# x-bus-expander.net
KiCad netlist of a schematic drawn in EAGLE
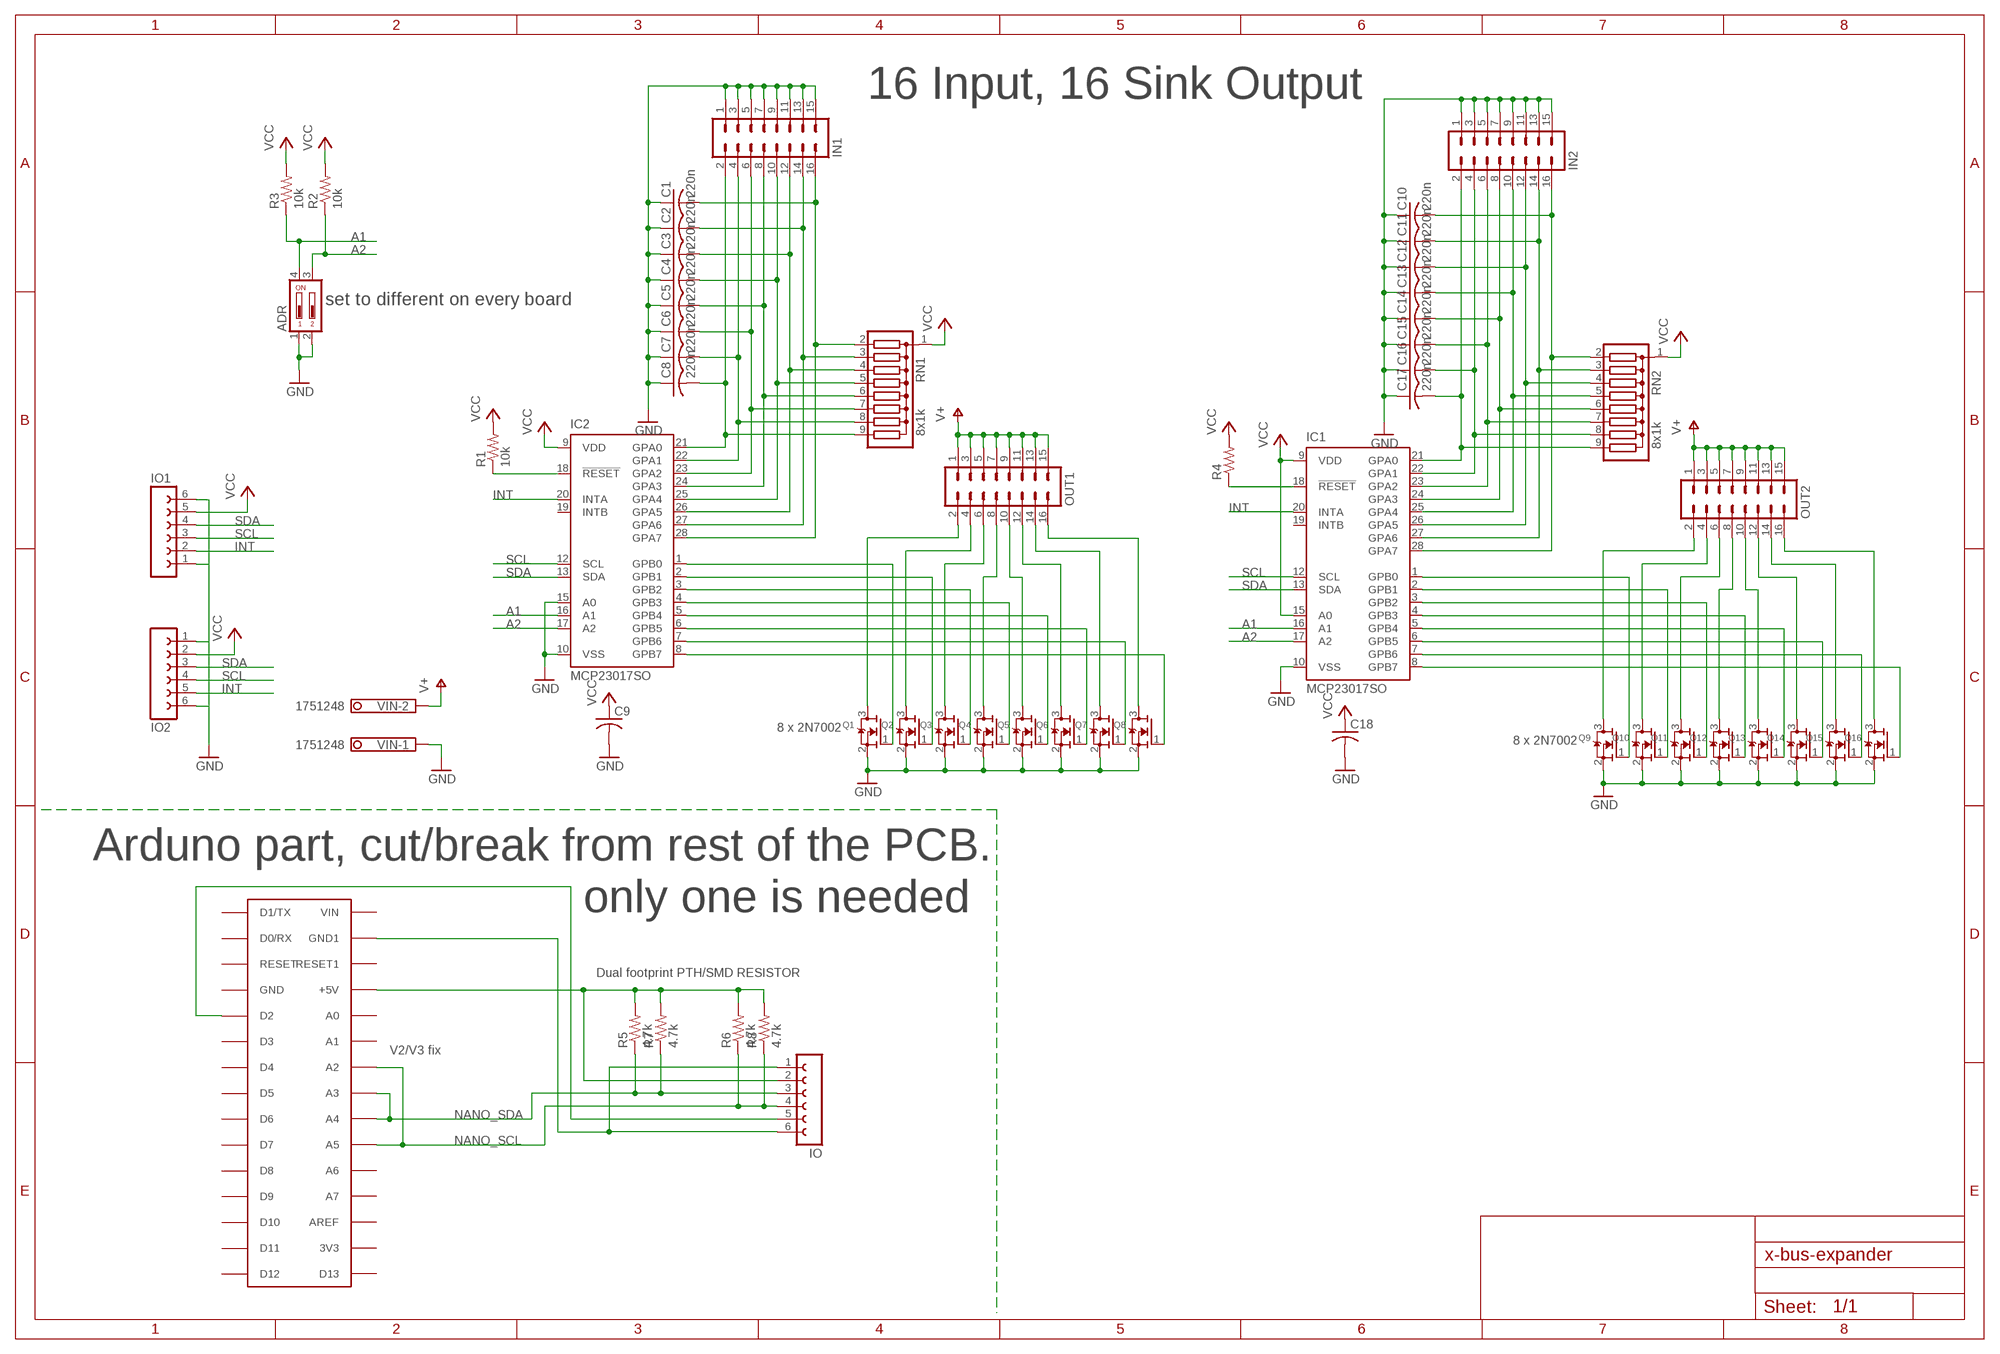
[diagram p0: schematic, sheet 1]

(export (version "E")
  (design (tool "Eeschema 10.0.6"))
  (components
    (comp (ref "ADR")
      (value "DIP02YL")
      (footprint "eagle-import:DIP02YL")
      (libsource (lib "eagle-import") (part "DIP02YL"))
    )
    (comp (ref "C1")
      (value "220n")
      (footprint "eagle-import:C0805")
      (libsource (lib "eagle-import") (part "C-USC0805"))
    )
    (comp (ref "C2")
      (value "220n")
      (footprint "eagle-import:C0805")
      (libsource (lib "eagle-import") (part "C-USC0805"))
    )
    (comp (ref "C3")
      (value "220n")
      (footprint "eagle-import:C0805")
      (libsource (lib "eagle-import") (part "C-USC0805"))
    )
    (comp (ref "C4")
      (value "220n")
      (footprint "eagle-import:C0805")
      (libsource (lib "eagle-import") (part "C-USC0805"))
    )
    (comp (ref "C5")
      (value "220n")
      (footprint "eagle-import:C0805")
      (libsource (lib "eagle-import") (part "C-USC0805"))
    )
    (comp (ref "C6")
      (value "220n")
      (footprint "eagle-import:C0805")
      (libsource (lib "eagle-import") (part "C-USC0805"))
    )
    (comp (ref "C7")
      (value "220n")
      (footprint "eagle-import:C0805")
      (libsource (lib "eagle-import") (part "C-USC0805"))
    )
    (comp (ref "C8")
      (value "220n")
      (footprint "eagle-import:C0805")
      (libsource (lib "eagle-import") (part "C-USC0805"))
    )
    (comp (ref "C9")
      (value "C-USC0805")
      (footprint "eagle-import:C0805")
      (libsource (lib "eagle-import") (part "C-USC0805"))
    )
    (comp (ref "C10")
      (value "220n")
      (footprint "eagle-import:C0805")
      (libsource (lib "eagle-import") (part "C-USC0805"))
    )
    (comp (ref "C11")
      (value "220n")
      (footprint "eagle-import:C0805")
      (libsource (lib "eagle-import") (part "C-USC0805"))
    )
    (comp (ref "C12")
      (value "220n")
      (footprint "eagle-import:C0805")
      (libsource (lib "eagle-import") (part "C-USC0805"))
    )
    (comp (ref "C13")
      (value "220n")
      (footprint "eagle-import:C0805")
      (libsource (lib "eagle-import") (part "C-USC0805"))
    )
    (comp (ref "C14")
      (value "220n")
      (footprint "eagle-import:C0805")
      (libsource (lib "eagle-import") (part "C-USC0805"))
    )
    (comp (ref "C15")
      (value "220n")
      (footprint "eagle-import:C0805")
      (libsource (lib "eagle-import") (part "C-USC0805"))
    )
    (comp (ref "C16")
      (value "220n")
      (footprint "eagle-import:C0805")
      (libsource (lib "eagle-import") (part "C-USC0805"))
    )
    (comp (ref "C17")
      (value "220n")
      (footprint "eagle-import:C0805")
      (libsource (lib "eagle-import") (part "C-USC0805"))
    )
    (comp (ref "C18")
      (value "C-USC0805")
      (footprint "eagle-import:C0805")
      (libsource (lib "eagle-import") (part "C-USC0805"))
    )
    (comp (ref "IC1")
      (value "MCP23017SO")
      (footprint "eagle-import:SO28W")
      (libsource (lib "eagle-import") (part "MCP23017SO"))
    )
    (comp (ref "IC2")
      (value "MCP23017SO")
      (footprint "eagle-import:SO28W")
      (libsource (lib "eagle-import") (part "MCP23017SO"))
    )
    (comp (ref "IN1")
      (value "ML16")
      (footprint "eagle-import:ML16")
      (libsource (lib "eagle-import") (part "ML16"))
    )
    (comp (ref "IN2")
      (value "ML16")
      (footprint "eagle-import:ML16")
      (libsource (lib "eagle-import") (part "ML16"))
    )
    (comp (ref "IO")
      (value "FE06W")
      (footprint "eagle-import:FE06W")
      (libsource (lib "eagle-import") (part "FE06W"))
    )
    (comp (ref "IO1")
      (value "FE06W")
      (footprint "eagle-import:FE06W")
      (libsource (lib "eagle-import") (part "FE06W"))
    )
    (comp (ref "IO2")
      (value "FE06W")
      (footprint "eagle-import:FE06W")
      (libsource (lib "eagle-import") (part "FE06W"))
    )
    (comp (ref "OUT1")
      (value "ML16")
      (footprint "eagle-import:ML16")
      (libsource (lib "eagle-import") (part "ML16"))
    )
    (comp (ref "OUT2")
      (value "ML16")
      (footprint "eagle-import:ML16")
      (libsource (lib "eagle-import") (part "ML16"))
    )
    (comp (ref "Q1")
      (value "MOSFET-NREFLOW")
      (footprint "eagle-import:SOT23")
      (libsource (lib "eagle-import") (part "MOSFET-NREFLOW"))
    )
    (comp (ref "Q2")
      (value "MOSFET-NREFLOW")
      (footprint "eagle-import:SOT23")
      (libsource (lib "eagle-import") (part "MOSFET-NREFLOW"))
    )
    (comp (ref "Q3")
      (value "MOSFET-NREFLOW")
      (footprint "eagle-import:SOT23")
      (libsource (lib "eagle-import") (part "MOSFET-NREFLOW"))
    )
    (comp (ref "Q4")
      (value "MOSFET-NREFLOW")
      (footprint "eagle-import:SOT23")
      (libsource (lib "eagle-import") (part "MOSFET-NREFLOW"))
    )
    (comp (ref "Q5")
      (value "MOSFET-NREFLOW")
      (footprint "eagle-import:SOT23")
      (libsource (lib "eagle-import") (part "MOSFET-NREFLOW"))
    )
    (comp (ref "Q6")
      (value "MOSFET-NREFLOW")
      (footprint "eagle-import:SOT23")
      (libsource (lib "eagle-import") (part "MOSFET-NREFLOW"))
    )
    (comp (ref "Q7")
      (value "MOSFET-NREFLOW")
      (footprint "eagle-import:SOT23")
      (libsource (lib "eagle-import") (part "MOSFET-NREFLOW"))
    )
    (comp (ref "Q8")
      (value "MOSFET-NREFLOW")
      (footprint "eagle-import:SOT23")
      (libsource (lib "eagle-import") (part "MOSFET-NREFLOW"))
    )
    (comp (ref "Q9")
      (value "MOSFET-NREFLOW")
      (footprint "eagle-import:SOT23")
      (libsource (lib "eagle-import") (part "MOSFET-NREFLOW"))
    )
    (comp (ref "Q10")
      (value "MOSFET-NREFLOW")
      (footprint "eagle-import:SOT23")
      (libsource (lib "eagle-import") (part "MOSFET-NREFLOW"))
    )
    (comp (ref "Q11")
      (value "MOSFET-NREFLOW")
      (footprint "eagle-import:SOT23")
      (libsource (lib "eagle-import") (part "MOSFET-NREFLOW"))
    )
    (comp (ref "Q12")
      (value "MOSFET-NREFLOW")
      (footprint "eagle-import:SOT23")
      (libsource (lib "eagle-import") (part "MOSFET-NREFLOW"))
    )
    (comp (ref "Q13")
      (value "MOSFET-NREFLOW")
      (footprint "eagle-import:SOT23")
      (libsource (lib "eagle-import") (part "MOSFET-NREFLOW"))
    )
    (comp (ref "Q14")
      (value "MOSFET-NREFLOW")
      (footprint "eagle-import:SOT23")
      (libsource (lib "eagle-import") (part "MOSFET-NREFLOW"))
    )
    (comp (ref "Q15")
      (value "MOSFET-NREFLOW")
      (footprint "eagle-import:SOT23")
      (libsource (lib "eagle-import") (part "MOSFET-NREFLOW"))
    )
    (comp (ref "Q16")
      (value "MOSFET-NREFLOW")
      (footprint "eagle-import:SOT23")
      (libsource (lib "eagle-import") (part "MOSFET-NREFLOW"))
    )
    (comp (ref "R1")
      (value "10k")
      (footprint "eagle-import:R0603")
      (libsource (lib "eagle-import") (part "R-US_R0603"))
    )
    (comp (ref "R2")
      (value "10k")
      (footprint "eagle-import:R0603")
      (libsource (lib "eagle-import") (part "R-US_R0603"))
    )
    (comp (ref "R3")
      (value "10k")
      (footprint "eagle-import:R0603")
      (libsource (lib "eagle-import") (part "R-US_R0603"))
    )
    (comp (ref "R4")
      (value "R-US_R0603")
      (footprint "eagle-import:R0603")
      (libsource (lib "eagle-import") (part "R-US_R0603"))
    )
    (comp (ref "R5")
      (value "4.7k")
      (footprint "eagle-import:0309_10")
      (libsource (lib "eagle-import") (part "R-US_0309/10"))
    )
    (comp (ref "R6")
      (value "4.7k")
      (footprint "eagle-import:0309_10")
      (libsource (lib "eagle-import") (part "R-US_0309/10"))
    )
    (comp (ref "R7")
      (value "4.7k")
      (footprint "eagle-import:R0603")
      (libsource (lib "eagle-import") (part "R-US_R0603"))
    )
    (comp (ref "R8")
      (value "4.7k")
      (footprint "eagle-import:R0603")
      (libsource (lib "eagle-import") (part "R-US_R0603"))
    )
    (comp (ref "RN1")
      (value "8x1k")
      (footprint "eagle-import:SIL9")
      (libsource (lib "eagle-import") (part "G08R"))
    )
    (comp (ref "RN2")
      (value "8x1k")
      (footprint "eagle-import:SIL9")
      (libsource (lib "eagle-import") (part "G08R"))
    )
    (comp (ref "U$1")
      (value "ARDUINONANO")
      (footprint "eagle-import:PDIP-32")
      (libsource (lib "eagle-import") (part "ARDUINONANO"))
    )
    (comp (ref "VIN")
      (value "1751248")
      (footprint "eagle-import:1751248")
      (libsource (lib "eagle-import") (part "1751248"))
    )
  )
  (nets
    (net (code "1") (name "/A1") (class "Default")
      (node (ref "ADR") (pin "4") (pinfunction "4_4") (pintype "passive"))
      (node (ref "IC1") (pin "16") (pinfunction "A1_16") (pintype "input"))
      (node (ref "IC2") (pin "16") (pinfunction "A1_16") (pintype "input"))
      (node (ref "R3") (pin "1") (pinfunction "1_1") (pintype "passive"))
    )
    (net (code "2") (name "/A2") (class "Default")
      (node (ref "ADR") (pin "3") (pinfunction "3_3") (pintype "passive"))
      (node (ref "IC1") (pin "17") (pinfunction "A2_17") (pintype "input"))
      (node (ref "IC2") (pin "17") (pinfunction "A2_17") (pintype "input"))
      (node (ref "R2") (pin "1") (pinfunction "1_1") (pintype "passive"))
    )
    (net (code "3") (name "/INT") (class "Default")
      (node (ref "IC1") (pin "20") (pinfunction "INTA_20") (pintype "output"))
      (node (ref "IC2") (pin "20") (pinfunction "INTA_20") (pintype "output"))
      (node (ref "IO1") (pin "2") (pinfunction "2_2") (pintype "passive"))
      (node (ref "IO2") (pin "5") (pinfunction "5_5") (pintype "passive"))
    )
    (net (code "4") (name "/NANO_SCL") (class "Default")
      (node (ref "IO") (pin "4") (pinfunction "4_4") (pintype "passive"))
      (node (ref "R6") (pin "1") (pinfunction "1_1") (pintype "passive"))
      (node (ref "R8") (pin "1") (pinfunction "1_1") (pintype "passive"))
      (node (ref "U$1") (pin "A2") (pinfunction "A2_A2") (pintype "bidirectional"))
      (node (ref "U$1") (pin "A5") (pinfunction "A5_A5") (pintype "bidirectional"))
    )
    (net (code "5") (name "/NANO_SDA") (class "Default")
      (node (ref "IO") (pin "3") (pinfunction "3_3") (pintype "passive"))
      (node (ref "R5") (pin "1") (pinfunction "1_1") (pintype "passive"))
      (node (ref "R7") (pin "1") (pinfunction "1_1") (pintype "passive"))
      (node (ref "U$1") (pin "A3") (pinfunction "A3_A3") (pintype "bidirectional"))
      (node (ref "U$1") (pin "A4") (pinfunction "A4_A4") (pintype "bidirectional"))
    )
    (net (code "6") (name "/SCL") (class "Default")
      (node (ref "IC1") (pin "12") (pinfunction "SCL_12") (pintype "input"))
      (node (ref "IC2") (pin "12") (pinfunction "SCL_12") (pintype "input"))
      (node (ref "IO1") (pin "3") (pinfunction "3_3") (pintype "passive"))
      (node (ref "IO2") (pin "4") (pinfunction "4_4") (pintype "passive"))
    )
    (net (code "7") (name "/SDA") (class "Default")
      (node (ref "IC1") (pin "13") (pinfunction "SDA_13") (pintype "bidirectional"))
      (node (ref "IC2") (pin "13") (pinfunction "SDA_13") (pintype "bidirectional"))
      (node (ref "IO1") (pin "4") (pinfunction "4_4") (pintype "passive"))
      (node (ref "IO2") (pin "3") (pinfunction "3_3") (pintype "passive"))
    )
    (net (code "8") (name "GND") (class "Default")
      (node (ref "ADR") (pin "1") (pinfunction "1_1") (pintype "passive"))
      (node (ref "ADR") (pin "2") (pinfunction "2_2") (pintype "passive"))
      (node (ref "C1") (pin "1") (pinfunction "1_1") (pintype "passive"))
      (node (ref "C10") (pin "1") (pinfunction "1_1") (pintype "passive"))
      (node (ref "C11") (pin "1") (pinfunction "1_1") (pintype "passive"))
      (node (ref "C12") (pin "1") (pinfunction "1_1") (pintype "passive"))
      (node (ref "C13") (pin "1") (pinfunction "1_1") (pintype "passive"))
      (node (ref "C14") (pin "1") (pinfunction "1_1") (pintype "passive"))
      (node (ref "C15") (pin "1") (pinfunction "1_1") (pintype "passive"))
      (node (ref "C16") (pin "1") (pinfunction "1_1") (pintype "passive"))
      (node (ref "C17") (pin "1") (pinfunction "1_1") (pintype "passive"))
      (node (ref "C18") (pin "2") (pinfunction "2_2") (pintype "passive"))
      (node (ref "C2") (pin "1") (pinfunction "1_1") (pintype "passive"))
      (node (ref "C3") (pin "1") (pinfunction "1_1") (pintype "passive"))
      (node (ref "C4") (pin "1") (pinfunction "1_1") (pintype "passive"))
      (node (ref "C5") (pin "1") (pinfunction "1_1") (pintype "passive"))
      (node (ref "C6") (pin "1") (pinfunction "1_1") (pintype "passive"))
      (node (ref "C7") (pin "1") (pinfunction "1_1") (pintype "passive"))
      (node (ref "C8") (pin "1") (pinfunction "1_1") (pintype "passive"))
      (node (ref "C9") (pin "2") (pinfunction "2_2") (pintype "passive"))
      (node (ref "IC1") (pin "10") (pinfunction "VSS_10") (pintype "power_in"))
      (node (ref "IC2") (pin "10") (pinfunction "VSS_10") (pintype "power_in"))
      (node (ref "IC2") (pin "15") (pinfunction "A0_15") (pintype "input"))
      (node (ref "IN1") (pin "1") (pinfunction "1_1") (pintype "passive"))
      (node (ref "IN1") (pin "11") (pinfunction "11_11") (pintype "passive"))
      (node (ref "IN1") (pin "13") (pinfunction "13_13") (pintype "passive"))
      (node (ref "IN1") (pin "15") (pinfunction "15_15") (pintype "passive"))
      (node (ref "IN1") (pin "3") (pinfunction "3_3") (pintype "passive"))
      (node (ref "IN1") (pin "5") (pinfunction "5_5") (pintype "passive"))
      (node (ref "IN1") (pin "7") (pinfunction "7_7") (pintype "passive"))
      (node (ref "IN1") (pin "9") (pinfunction "9_9") (pintype "passive"))
      (node (ref "IN2") (pin "1") (pinfunction "1_1") (pintype "passive"))
      (node (ref "IN2") (pin "11") (pinfunction "11_11") (pintype "passive"))
      (node (ref "IN2") (pin "13") (pinfunction "13_13") (pintype "passive"))
      (node (ref "IN2") (pin "15") (pinfunction "15_15") (pintype "passive"))
      (node (ref "IN2") (pin "3") (pinfunction "3_3") (pintype "passive"))
      (node (ref "IN2") (pin "5") (pinfunction "5_5") (pintype "passive"))
      (node (ref "IN2") (pin "7") (pinfunction "7_7") (pintype "passive"))
      (node (ref "IN2") (pin "9") (pinfunction "9_9") (pintype "passive"))
      (node (ref "IO1") (pin "1") (pinfunction "1_1") (pintype "passive"))
      (node (ref "IO1") (pin "6") (pinfunction "6_6") (pintype "passive"))
      (node (ref "IO2") (pin "1") (pinfunction "1_1") (pintype "passive"))
      (node (ref "IO2") (pin "6") (pinfunction "6_6") (pintype "passive"))
      (node (ref "Q1") (pin "2") (pinfunction "S_2") (pintype "bidirectional"))
      (node (ref "Q10") (pin "2") (pinfunction "S_2") (pintype "bidirectional"))
      (node (ref "Q11") (pin "2") (pinfunction "S_2") (pintype "bidirectional"))
      (node (ref "Q12") (pin "2") (pinfunction "S_2") (pintype "bidirectional"))
      (node (ref "Q13") (pin "2") (pinfunction "S_2") (pintype "bidirectional"))
      (node (ref "Q14") (pin "2") (pinfunction "S_2") (pintype "bidirectional"))
      (node (ref "Q15") (pin "2") (pinfunction "S_2") (pintype "bidirectional"))
      (node (ref "Q16") (pin "2") (pinfunction "S_2") (pintype "bidirectional"))
      (node (ref "Q2") (pin "2") (pinfunction "S_2") (pintype "bidirectional"))
      (node (ref "Q3") (pin "2") (pinfunction "S_2") (pintype "bidirectional"))
      (node (ref "Q4") (pin "2") (pinfunction "S_2") (pintype "bidirectional"))
      (node (ref "Q5") (pin "2") (pinfunction "S_2") (pintype "bidirectional"))
      (node (ref "Q6") (pin "2") (pinfunction "S_2") (pintype "bidirectional"))
      (node (ref "Q7") (pin "2") (pinfunction "S_2") (pintype "bidirectional"))
      (node (ref "Q8") (pin "2") (pinfunction "S_2") (pintype "bidirectional"))
      (node (ref "Q9") (pin "2") (pinfunction "S_2") (pintype "bidirectional"))
      (node (ref "VIN") (pin "1") (pinfunction "K_1") (pintype "passive"))
    )
    (net (code "9") (name "Net-(IC1-GPA0)") (class "Default")
      (node (ref "C17") (pin "2") (pinfunction "2_2") (pintype "passive"))
      (node (ref "IC1") (pin "21") (pinfunction "GPA0_21") (pintype "bidirectional"))
      (node (ref "IN2") (pin "2") (pinfunction "2_2") (pintype "passive"))
      (node (ref "RN2") (pin "9") (pinfunction "9_9") (pintype "passive"))
    )
    (net (code "10") (name "Net-(IC1-GPA1)") (class "Default")
      (node (ref "C16") (pin "2") (pinfunction "2_2") (pintype "passive"))
      (node (ref "IC1") (pin "22") (pinfunction "GPA1_22") (pintype "bidirectional"))
      (node (ref "IN2") (pin "4") (pinfunction "4_4") (pintype "passive"))
      (node (ref "RN2") (pin "8") (pinfunction "8_8") (pintype "passive"))
    )
    (net (code "11") (name "Net-(IC1-GPA2)") (class "Default")
      (node (ref "C15") (pin "2") (pinfunction "2_2") (pintype "passive"))
      (node (ref "IC1") (pin "23") (pinfunction "GPA2_23") (pintype "bidirectional"))
      (node (ref "IN2") (pin "6") (pinfunction "6_6") (pintype "passive"))
      (node (ref "RN2") (pin "7") (pinfunction "7_7") (pintype "passive"))
    )
    (net (code "12") (name "Net-(IC1-GPA3)") (class "Default")
      (node (ref "C14") (pin "2") (pinfunction "2_2") (pintype "passive"))
      (node (ref "IC1") (pin "24") (pinfunction "GPA3_24") (pintype "bidirectional"))
      (node (ref "IN2") (pin "8") (pinfunction "8_8") (pintype "passive"))
      (node (ref "RN2") (pin "6") (pinfunction "6_6") (pintype "passive"))
    )
    (net (code "13") (name "Net-(IC1-GPA4)") (class "Default")
      (node (ref "C13") (pin "2") (pinfunction "2_2") (pintype "passive"))
      (node (ref "IC1") (pin "25") (pinfunction "GPA4_25") (pintype "bidirectional"))
      (node (ref "IN2") (pin "10") (pinfunction "10_10") (pintype "passive"))
      (node (ref "RN2") (pin "5") (pinfunction "5_5") (pintype "passive"))
    )
    (net (code "14") (name "Net-(IC1-GPA5)") (class "Default")
      (node (ref "C12") (pin "2") (pinfunction "2_2") (pintype "passive"))
      (node (ref "IC1") (pin "26") (pinfunction "GPA5_26") (pintype "bidirectional"))
      (node (ref "IN2") (pin "12") (pinfunction "12_12") (pintype "passive"))
      (node (ref "RN2") (pin "4") (pinfunction "4_4") (pintype "passive"))
    )
    (net (code "15") (name "Net-(IC1-GPA6)") (class "Default")
      (node (ref "C11") (pin "2") (pinfunction "2_2") (pintype "passive"))
      (node (ref "IC1") (pin "27") (pinfunction "GPA6_27") (pintype "bidirectional"))
      (node (ref "IN2") (pin "14") (pinfunction "14_14") (pintype "passive"))
      (node (ref "RN2") (pin "3") (pinfunction "3_3") (pintype "passive"))
    )
    (net (code "16") (name "Net-(IC1-GPA7)") (class "Default")
      (node (ref "C10") (pin "2") (pinfunction "2_2") (pintype "passive"))
      (node (ref "IC1") (pin "28") (pinfunction "GPA7_28") (pintype "bidirectional"))
      (node (ref "IN2") (pin "16") (pinfunction "16_16") (pintype "passive"))
      (node (ref "RN2") (pin "2") (pinfunction "2_2") (pintype "passive"))
    )
    (net (code "17") (name "Net-(IC1-GPB0)") (class "Default")
      (node (ref "IC1") (pin "1") (pinfunction "GPB0_1") (pintype "bidirectional"))
      (node (ref "Q9") (pin "1") (pinfunction "G_1") (pintype "bidirectional"))
    )
    (net (code "18") (name "Net-(IC1-GPB1)") (class "Default")
      (node (ref "IC1") (pin "2") (pinfunction "GPB1_2") (pintype "bidirectional"))
      (node (ref "Q10") (pin "1") (pinfunction "G_1") (pintype "bidirectional"))
    )
    (net (code "19") (name "Net-(IC1-GPB2)") (class "Default")
      (node (ref "IC1") (pin "3") (pinfunction "GPB2_3") (pintype "bidirectional"))
      (node (ref "Q11") (pin "1") (pinfunction "G_1") (pintype "bidirectional"))
    )
    (net (code "20") (name "Net-(IC1-GPB3)") (class "Default")
      (node (ref "IC1") (pin "4") (pinfunction "GPB3_4") (pintype "bidirectional"))
      (node (ref "Q12") (pin "1") (pinfunction "G_1") (pintype "bidirectional"))
    )
    (net (code "21") (name "Net-(IC1-GPB4)") (class "Default")
      (node (ref "IC1") (pin "5") (pinfunction "GPB4_5") (pintype "bidirectional"))
      (node (ref "Q13") (pin "1") (pinfunction "G_1") (pintype "bidirectional"))
    )
    (net (code "22") (name "Net-(IC1-GPB5)") (class "Default")
      (node (ref "IC1") (pin "6") (pinfunction "GPB5_6") (pintype "bidirectional"))
      (node (ref "Q14") (pin "1") (pinfunction "G_1") (pintype "bidirectional"))
    )
    (net (code "23") (name "Net-(IC1-GPB6)") (class "Default")
      (node (ref "IC1") (pin "7") (pinfunction "GPB6_7") (pintype "bidirectional"))
      (node (ref "Q15") (pin "1") (pinfunction "G_1") (pintype "bidirectional"))
    )
    (net (code "24") (name "Net-(IC1-GPB7)") (class "Default")
      (node (ref "IC1") (pin "8") (pinfunction "GPB7_8") (pintype "bidirectional"))
      (node (ref "Q16") (pin "1") (pinfunction "G_1") (pintype "bidirectional"))
    )
    (net (code "25") (name "Net-(IC1-~{RESET})") (class "Default")
      (node (ref "IC1") (pin "18") (pinfunction "~{RESET}_18") (pintype "input"))
      (node (ref "R4") (pin "1") (pinfunction "1_1") (pintype "passive"))
    )
    (net (code "26") (name "Net-(IC2-GPA0)") (class "Default")
      (node (ref "C8") (pin "2") (pinfunction "2_2") (pintype "passive"))
      (node (ref "IC2") (pin "21") (pinfunction "GPA0_21") (pintype "bidirectional"))
      (node (ref "IN1") (pin "2") (pinfunction "2_2") (pintype "passive"))
      (node (ref "RN1") (pin "9") (pinfunction "9_9") (pintype "passive"))
    )
    (net (code "27") (name "Net-(IC2-GPA1)") (class "Default")
      (node (ref "C7") (pin "2") (pinfunction "2_2") (pintype "passive"))
      (node (ref "IC2") (pin "22") (pinfunction "GPA1_22") (pintype "bidirectional"))
      (node (ref "IN1") (pin "4") (pinfunction "4_4") (pintype "passive"))
      (node (ref "RN1") (pin "8") (pinfunction "8_8") (pintype "passive"))
    )
    (net (code "28") (name "Net-(IC2-GPA2)") (class "Default")
      (node (ref "C6") (pin "2") (pinfunction "2_2") (pintype "passive"))
      (node (ref "IC2") (pin "23") (pinfunction "GPA2_23") (pintype "bidirectional"))
      (node (ref "IN1") (pin "6") (pinfunction "6_6") (pintype "passive"))
      (node (ref "RN1") (pin "7") (pinfunction "7_7") (pintype "passive"))
    )
    (net (code "29") (name "Net-(IC2-GPA3)") (class "Default")
      (node (ref "C5") (pin "2") (pinfunction "2_2") (pintype "passive"))
      (node (ref "IC2") (pin "24") (pinfunction "GPA3_24") (pintype "bidirectional"))
      (node (ref "IN1") (pin "8") (pinfunction "8_8") (pintype "passive"))
      (node (ref "RN1") (pin "6") (pinfunction "6_6") (pintype "passive"))
    )
    (net (code "30") (name "Net-(IC2-GPA4)") (class "Default")
      (node (ref "C4") (pin "2") (pinfunction "2_2") (pintype "passive"))
      (node (ref "IC2") (pin "25") (pinfunction "GPA4_25") (pintype "bidirectional"))
      (node (ref "IN1") (pin "10") (pinfunction "10_10") (pintype "passive"))
      (node (ref "RN1") (pin "5") (pinfunction "5_5") (pintype "passive"))
    )
    (net (code "31") (name "Net-(IC2-GPA5)") (class "Default")
      (node (ref "C3") (pin "2") (pinfunction "2_2") (pintype "passive"))
      (node (ref "IC2") (pin "26") (pinfunction "GPA5_26") (pintype "bidirectional"))
      (node (ref "IN1") (pin "12") (pinfunction "12_12") (pintype "passive"))
      (node (ref "RN1") (pin "4") (pinfunction "4_4") (pintype "passive"))
    )
    (net (code "32") (name "Net-(IC2-GPA6)") (class "Default")
      (node (ref "C2") (pin "2") (pinfunction "2_2") (pintype "passive"))
      (node (ref "IC2") (pin "27") (pinfunction "GPA6_27") (pintype "bidirectional"))
      (node (ref "IN1") (pin "14") (pinfunction "14_14") (pintype "passive"))
      (node (ref "RN1") (pin "3") (pinfunction "3_3") (pintype "passive"))
    )
    (net (code "33") (name "Net-(IC2-GPA7)") (class "Default")
      (node (ref "C1") (pin "2") (pinfunction "2_2") (pintype "passive"))
      (node (ref "IC2") (pin "28") (pinfunction "GPA7_28") (pintype "bidirectional"))
      (node (ref "IN1") (pin "16") (pinfunction "16_16") (pintype "passive"))
      (node (ref "RN1") (pin "2") (pinfunction "2_2") (pintype "passive"))
    )
    (net (code "34") (name "Net-(IC2-GPB0)") (class "Default")
      (node (ref "IC2") (pin "1") (pinfunction "GPB0_1") (pintype "bidirectional"))
      (node (ref "Q1") (pin "1") (pinfunction "G_1") (pintype "bidirectional"))
    )
    (net (code "35") (name "Net-(IC2-GPB1)") (class "Default")
      (node (ref "IC2") (pin "2") (pinfunction "GPB1_2") (pintype "bidirectional"))
      (node (ref "Q2") (pin "1") (pinfunction "G_1") (pintype "bidirectional"))
    )
    (net (code "36") (name "Net-(IC2-GPB2)") (class "Default")
      (node (ref "IC2") (pin "3") (pinfunction "GPB2_3") (pintype "bidirectional"))
      (node (ref "Q3") (pin "1") (pinfunction "G_1") (pintype "bidirectional"))
    )
    (net (code "37") (name "Net-(IC2-GPB3)") (class "Default")
      (node (ref "IC2") (pin "4") (pinfunction "GPB3_4") (pintype "bidirectional"))
      (node (ref "Q4") (pin "1") (pinfunction "G_1") (pintype "bidirectional"))
    )
    (net (code "38") (name "Net-(IC2-GPB4)") (class "Default")
      (node (ref "IC2") (pin "5") (pinfunction "GPB4_5") (pintype "bidirectional"))
      (node (ref "Q5") (pin "1") (pinfunction "G_1") (pintype "bidirectional"))
    )
    (net (code "39") (name "Net-(IC2-GPB5)") (class "Default")
      (node (ref "IC2") (pin "6") (pinfunction "GPB5_6") (pintype "bidirectional"))
      (node (ref "Q6") (pin "1") (pinfunction "G_1") (pintype "bidirectional"))
    )
    (net (code "40") (name "Net-(IC2-GPB6)") (class "Default")
      (node (ref "IC2") (pin "7") (pinfunction "GPB6_7") (pintype "bidirectional"))
      (node (ref "Q7") (pin "1") (pinfunction "G_1") (pintype "bidirectional"))
    )
    (net (code "41") (name "Net-(IC2-GPB7)") (class "Default")
      (node (ref "IC2") (pin "8") (pinfunction "GPB7_8") (pintype "bidirectional"))
      (node (ref "Q8") (pin "1") (pinfunction "G_1") (pintype "bidirectional"))
    )
    (net (code "42") (name "Net-(IC2-~{RESET})") (class "Default")
      (node (ref "IC2") (pin "18") (pinfunction "~{RESET}_18") (pintype "input"))
      (node (ref "R1") (pin "1") (pinfunction "1_1") (pintype "passive"))
    )
    (net (code "43") (name "Net-(IO-Pad1)") (class "Default")
      (node (ref "IO") (pin "1") (pinfunction "1_1") (pintype "passive"))
      (node (ref "IO") (pin "6") (pinfunction "6_6") (pintype "passive"))
      (node (ref "U$1") (pin "GND1") (pinfunction "GND1_GND1") (pintype "bidirectional"))
    )
    (net (code "44") (name "Net-(IO-Pad2)") (class "Default")
      (node (ref "IO") (pin "2") (pinfunction "2_2") (pintype "passive"))
      (node (ref "R5") (pin "2") (pinfunction "2_2") (pintype "passive"))
      (node (ref "R6") (pin "2") (pinfunction "2_2") (pintype "passive"))
      (node (ref "R7") (pin "2") (pinfunction "2_2") (pintype "passive"))
      (node (ref "R8") (pin "2") (pinfunction "2_2") (pintype "passive"))
      (node (ref "U$1") (pin "+5V") (pinfunction "+5V_+5V") (pintype "bidirectional"))
    )
    (net (code "45") (name "Net-(IO-Pad5)") (class "Default")
      (node (ref "IO") (pin "5") (pinfunction "5_5") (pintype "passive"))
      (node (ref "U$1") (pin "D2") (pinfunction "D2_D2") (pintype "bidirectional"))
    )
    (net (code "46") (name "Net-(Q1-D)") (class "Default")
      (node (ref "OUT1") (pin "2") (pinfunction "2_2") (pintype "passive"))
      (node (ref "Q1") (pin "3") (pinfunction "D_3") (pintype "bidirectional"))
    )
    (net (code "47") (name "Net-(Q2-D)") (class "Default")
      (node (ref "OUT1") (pin "4") (pinfunction "4_4") (pintype "passive"))
      (node (ref "Q2") (pin "3") (pinfunction "D_3") (pintype "bidirectional"))
    )
    (net (code "48") (name "Net-(Q3-D)") (class "Default")
      (node (ref "OUT1") (pin "6") (pinfunction "6_6") (pintype "passive"))
      (node (ref "Q3") (pin "3") (pinfunction "D_3") (pintype "bidirectional"))
    )
    (net (code "49") (name "Net-(Q4-D)") (class "Default")
      (node (ref "OUT1") (pin "8") (pinfunction "8_8") (pintype "passive"))
      (node (ref "Q4") (pin "3") (pinfunction "D_3") (pintype "bidirectional"))
    )
    (net (code "50") (name "Net-(Q5-D)") (class "Default")
      (node (ref "OUT1") (pin "10") (pinfunction "10_10") (pintype "passive"))
      (node (ref "Q5") (pin "3") (pinfunction "D_3") (pintype "bidirectional"))
    )
    (net (code "51") (name "Net-(Q6-D)") (class "Default")
      (node (ref "OUT1") (pin "12") (pinfunction "12_12") (pintype "passive"))
      (node (ref "Q6") (pin "3") (pinfunction "D_3") (pintype "bidirectional"))
    )
    (net (code "52") (name "Net-(Q7-D)") (class "Default")
      (node (ref "OUT1") (pin "14") (pinfunction "14_14") (pintype "passive"))
      (node (ref "Q7") (pin "3") (pinfunction "D_3") (pintype "bidirectional"))
    )
    (net (code "53") (name "Net-(Q8-D)") (class "Default")
      (node (ref "OUT1") (pin "16") (pinfunction "16_16") (pintype "passive"))
      (node (ref "Q8") (pin "3") (pinfunction "D_3") (pintype "bidirectional"))
    )
    (net (code "54") (name "Net-(Q9-D)") (class "Default")
      (node (ref "OUT2") (pin "2") (pinfunction "2_2") (pintype "passive"))
      (node (ref "Q9") (pin "3") (pinfunction "D_3") (pintype "bidirectional"))
    )
    (net (code "55") (name "Net-(Q10-D)") (class "Default")
      (node (ref "OUT2") (pin "4") (pinfunction "4_4") (pintype "passive"))
      (node (ref "Q10") (pin "3") (pinfunction "D_3") (pintype "bidirectional"))
    )
    (net (code "56") (name "Net-(Q11-D)") (class "Default")
      (node (ref "OUT2") (pin "6") (pinfunction "6_6") (pintype "passive"))
      (node (ref "Q11") (pin "3") (pinfunction "D_3") (pintype "bidirectional"))
    )
    (net (code "57") (name "Net-(Q12-D)") (class "Default")
      (node (ref "OUT2") (pin "8") (pinfunction "8_8") (pintype "passive"))
      (node (ref "Q12") (pin "3") (pinfunction "D_3") (pintype "bidirectional"))
    )
    (net (code "58") (name "Net-(Q13-D)") (class "Default")
      (node (ref "OUT2") (pin "10") (pinfunction "10_10") (pintype "passive"))
      (node (ref "Q13") (pin "3") (pinfunction "D_3") (pintype "bidirectional"))
    )
    (net (code "59") (name "Net-(Q14-D)") (class "Default")
      (node (ref "OUT2") (pin "12") (pinfunction "12_12") (pintype "passive"))
      (node (ref "Q14") (pin "3") (pinfunction "D_3") (pintype "bidirectional"))
    )
    (net (code "60") (name "Net-(Q15-D)") (class "Default")
      (node (ref "OUT2") (pin "14") (pinfunction "14_14") (pintype "passive"))
      (node (ref "Q15") (pin "3") (pinfunction "D_3") (pintype "bidirectional"))
    )
    (net (code "61") (name "Net-(Q16-D)") (class "Default")
      (node (ref "OUT2") (pin "16") (pinfunction "16_16") (pintype "passive"))
      (node (ref "Q16") (pin "3") (pinfunction "D_3") (pintype "bidirectional"))
    )
    (net (code "62") (name "V+") (class "Default")
      (node (ref "OUT1") (pin "1") (pinfunction "1_1") (pintype "passive"))
      (node (ref "OUT1") (pin "11") (pinfunction "11_11") (pintype "passive"))
      (node (ref "OUT1") (pin "13") (pinfunction "13_13") (pintype "passive"))
      (node (ref "OUT1") (pin "15") (pinfunction "15_15") (pintype "passive"))
      (node (ref "OUT1") (pin "3") (pinfunction "3_3") (pintype "passive"))
      (node (ref "OUT1") (pin "5") (pinfunction "5_5") (pintype "passive"))
      (node (ref "OUT1") (pin "7") (pinfunction "7_7") (pintype "passive"))
      (node (ref "OUT1") (pin "9") (pinfunction "9_9") (pintype "passive"))
      (node (ref "OUT2") (pin "1") (pinfunction "1_1") (pintype "passive"))
      (node (ref "OUT2") (pin "11") (pinfunction "11_11") (pintype "passive"))
      (node (ref "OUT2") (pin "13") (pinfunction "13_13") (pintype "passive"))
      (node (ref "OUT2") (pin "15") (pinfunction "15_15") (pintype "passive"))
      (node (ref "OUT2") (pin "3") (pinfunction "3_3") (pintype "passive"))
      (node (ref "OUT2") (pin "5") (pinfunction "5_5") (pintype "passive"))
      (node (ref "OUT2") (pin "7") (pinfunction "7_7") (pintype "passive"))
      (node (ref "OUT2") (pin "9") (pinfunction "9_9") (pintype "passive"))
      (node (ref "VIN") (pin "2") (pinfunction "K_2") (pintype "passive"))
    )
    (net (code "63") (name "VCC") (class "Default")
      (node (ref "C18") (pin "1") (pinfunction "1_1") (pintype "passive"))
      (node (ref "C9") (pin "1") (pinfunction "1_1") (pintype "passive"))
      (node (ref "IC1") (pin "15") (pinfunction "A0_15") (pintype "input"))
      (node (ref "IC1") (pin "9") (pinfunction "VDD_9") (pintype "power_in"))
      (node (ref "IC2") (pin "9") (pinfunction "VDD_9") (pintype "power_in"))
      (node (ref "IO1") (pin "5") (pinfunction "5_5") (pintype "passive"))
      (node (ref "IO2") (pin "2") (pinfunction "2_2") (pintype "passive"))
      (node (ref "R1") (pin "2") (pinfunction "2_2") (pintype "passive"))
      (node (ref "R2") (pin "2") (pinfunction "2_2") (pintype "passive"))
      (node (ref "R3") (pin "2") (pinfunction "2_2") (pintype "passive"))
      (node (ref "R4") (pin "2") (pinfunction "2_2") (pintype "passive"))
      (node (ref "RN1") (pin "1") (pinfunction "1_1") (pintype "passive"))
      (node (ref "RN2") (pin "1") (pinfunction "1_1") (pintype "passive"))
    )
    (net (code "64") (name "unconnected-(IC1-INTB-Pad19)") (class "Default")
      (node (ref "IC1") (pin "19") (pinfunction "INTB_19") (pintype "output"))
    )
    (net (code "65") (name "unconnected-(IC2-INTB-Pad19)") (class "Default")
      (node (ref "IC2") (pin "19") (pinfunction "INTB_19") (pintype "output"))
    )
    (net (code "66") (name "unconnected-(U$1-Pad3V3)") (class "Default")
      (node (ref "U$1") (pin "3V3") (pinfunction "3V3_3V3") (pintype "bidirectional"))
    )
    (net (code "67") (name "unconnected-(U$1-PadA0)") (class "Default")
      (node (ref "U$1") (pin "A0") (pinfunction "A0_A0") (pintype "bidirectional"))
    )
    (net (code "68") (name "unconnected-(U$1-PadA1)") (class "Default")
      (node (ref "U$1") (pin "A1") (pinfunction "A1_A1") (pintype "bidirectional"))
    )
    (net (code "69") (name "unconnected-(U$1-PadA6)") (class "Default")
      (node (ref "U$1") (pin "A6") (pinfunction "A6_A6") (pintype "bidirectional"))
    )
    (net (code "70") (name "unconnected-(U$1-PadA7)") (class "Default")
      (node (ref "U$1") (pin "A7") (pinfunction "A7_A7") (pintype "bidirectional"))
    )
    (net (code "71") (name "unconnected-(U$1-PadAREF)") (class "Default")
      (node (ref "U$1") (pin "AREF") (pinfunction "AREF_AREF") (pintype "bidirectional"))
    )
    (net (code "72") (name "unconnected-(U$1-PadD0{slash}RX)") (class "Default")
      (node (ref "U$1") (pin "D0/RX") (pinfunction "D0/RX_D0/RX") (pintype "bidirectional"))
    )
    (net (code "73") (name "unconnected-(U$1-PadD1{slash}TX)") (class "Default")
      (node (ref "U$1") (pin "D1/TX") (pinfunction "D1/TX_D1/TX") (pintype "bidirectional"))
    )
    (net (code "74") (name "unconnected-(U$1-PadD3)") (class "Default")
      (node (ref "U$1") (pin "D3") (pinfunction "D3_D3") (pintype "bidirectional"))
    )
    (net (code "75") (name "unconnected-(U$1-PadD4)") (class "Default")
      (node (ref "U$1") (pin "D4") (pinfunction "D4_D4") (pintype "bidirectional"))
    )
    (net (code "76") (name "unconnected-(U$1-PadD5)") (class "Default")
      (node (ref "U$1") (pin "D5") (pinfunction "D5_D5") (pintype "bidirectional"))
    )
    (net (code "77") (name "unconnected-(U$1-PadD6)") (class "Default")
      (node (ref "U$1") (pin "D6") (pinfunction "D6_D6") (pintype "bidirectional"))
    )
    (net (code "78") (name "unconnected-(U$1-PadD7)") (class "Default")
      (node (ref "U$1") (pin "D7") (pinfunction "D7_D7") (pintype "bidirectional"))
    )
    (net (code "79") (name "unconnected-(U$1-PadD8)") (class "Default")
      (node (ref "U$1") (pin "D8") (pinfunction "D8_D8") (pintype "bidirectional"))
    )
    (net (code "80") (name "unconnected-(U$1-PadD9)") (class "Default")
      (node (ref "U$1") (pin "D9") (pinfunction "D9_D9") (pintype "bidirectional"))
    )
    (net (code "81") (name "unconnected-(U$1-PadD10)") (class "Default")
      (node (ref "U$1") (pin "D10") (pinfunction "D10_D10") (pintype "bidirectional"))
    )
    (net (code "82") (name "unconnected-(U$1-PadD11)") (class "Default")
      (node (ref "U$1") (pin "D11") (pinfunction "D11_D11") (pintype "bidirectional"))
    )
    (net (code "83") (name "unconnected-(U$1-PadD12)") (class "Default")
      (node (ref "U$1") (pin "D12") (pinfunction "D12_D12") (pintype "bidirectional"))
    )
    (net (code "84") (name "unconnected-(U$1-PadD13)") (class "Default")
      (node (ref "U$1") (pin "D13") (pinfunction "D13_D13") (pintype "bidirectional"))
    )
    (net (code "85") (name "unconnected-(U$1-PadGND)") (class "Default")
      (node (ref "U$1") (pin "GND") (pinfunction "GND_GND") (pintype "bidirectional"))
    )
    (net (code "86") (name "unconnected-(U$1-PadRESET)") (class "Default")
      (node (ref "U$1") (pin "RESET") (pinfunction "RESET_RESET") (pintype "bidirectional"))
    )
    (net (code "87") (name "unconnected-(U$1-PadRESET1)") (class "Default")
      (node (ref "U$1") (pin "RESET1") (pinfunction "RESET1_RESET1") (pintype "bidirectional"))
    )
    (net (code "88") (name "unconnected-(U$1-PadVIN)") (class "Default")
      (node (ref "U$1") (pin "VIN") (pinfunction "VIN_VIN") (pintype "bidirectional"))
    )
  )
)
